# addr-bl.net
KiCad netlist of a schematic drawn in EAGLE
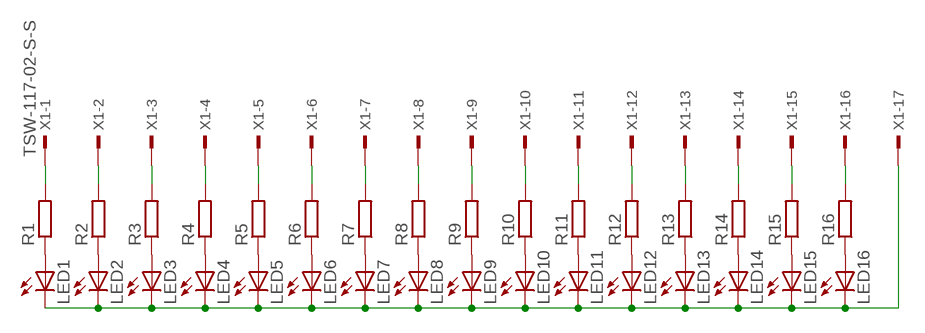
[diagram p0: schematic, sheet 1]

(export (version "E")
  (design (tool "Eeschema 10.0.6"))
  (components
    (comp (ref "LED1")
      (value "LEDSMT1206")
      (footprint "eagle-import:1206")
      (libsource (lib "eagle-import") (part "LEDSMT1206"))
    )
    (comp (ref "LED2")
      (value "LEDSMT1206")
      (footprint "eagle-import:1206")
      (libsource (lib "eagle-import") (part "LEDSMT1206"))
    )
    (comp (ref "LED3")
      (value "LEDSMT1206")
      (footprint "eagle-import:1206")
      (libsource (lib "eagle-import") (part "LEDSMT1206"))
    )
    (comp (ref "LED4")
      (value "LEDSMT1206")
      (footprint "eagle-import:1206")
      (libsource (lib "eagle-import") (part "LEDSMT1206"))
    )
    (comp (ref "LED5")
      (value "LEDSMT1206")
      (footprint "eagle-import:1206")
      (libsource (lib "eagle-import") (part "LEDSMT1206"))
    )
    (comp (ref "LED6")
      (value "LEDSMT1206")
      (footprint "eagle-import:1206")
      (libsource (lib "eagle-import") (part "LEDSMT1206"))
    )
    (comp (ref "LED7")
      (value "LEDSMT1206")
      (footprint "eagle-import:1206")
      (libsource (lib "eagle-import") (part "LEDSMT1206"))
    )
    (comp (ref "LED8")
      (value "LEDSMT1206")
      (footprint "eagle-import:1206")
      (libsource (lib "eagle-import") (part "LEDSMT1206"))
    )
    (comp (ref "LED9")
      (value "LEDSMT1206")
      (footprint "eagle-import:1206")
      (libsource (lib "eagle-import") (part "LEDSMT1206"))
    )
    (comp (ref "LED10")
      (value "LEDSMT1206")
      (footprint "eagle-import:1206")
      (libsource (lib "eagle-import") (part "LEDSMT1206"))
    )
    (comp (ref "LED11")
      (value "LEDSMT1206")
      (footprint "eagle-import:1206")
      (libsource (lib "eagle-import") (part "LEDSMT1206"))
    )
    (comp (ref "LED12")
      (value "LEDSMT1206")
      (footprint "eagle-import:1206")
      (libsource (lib "eagle-import") (part "LEDSMT1206"))
    )
    (comp (ref "LED13")
      (value "LEDSMT1206")
      (footprint "eagle-import:1206")
      (libsource (lib "eagle-import") (part "LEDSMT1206"))
    )
    (comp (ref "LED14")
      (value "LEDSMT1206")
      (footprint "eagle-import:1206")
      (libsource (lib "eagle-import") (part "LEDSMT1206"))
    )
    (comp (ref "LED15")
      (value "LEDSMT1206")
      (footprint "eagle-import:1206")
      (libsource (lib "eagle-import") (part "LEDSMT1206"))
    )
    (comp (ref "LED16")
      (value "LEDSMT1206")
      (footprint "eagle-import:1206")
      (libsource (lib "eagle-import") (part "LEDSMT1206"))
    )
    (comp (ref "R1")
      (value "R-EU_M1206")
      (footprint "eagle-import:M1206")
      (libsource (lib "eagle-import") (part "R-EU_M1206"))
    )
    (comp (ref "R2")
      (value "R-EU_M1206")
      (footprint "eagle-import:M1206")
      (libsource (lib "eagle-import") (part "R-EU_M1206"))
    )
    (comp (ref "R3")
      (value "R-EU_M1206")
      (footprint "eagle-import:M1206")
      (libsource (lib "eagle-import") (part "R-EU_M1206"))
    )
    (comp (ref "R4")
      (value "R-EU_M1206")
      (footprint "eagle-import:M1206")
      (libsource (lib "eagle-import") (part "R-EU_M1206"))
    )
    (comp (ref "R5")
      (value "R-EU_M1206")
      (footprint "eagle-import:M1206")
      (libsource (lib "eagle-import") (part "R-EU_M1206"))
    )
    (comp (ref "R6")
      (value "R-EU_M1206")
      (footprint "eagle-import:M1206")
      (libsource (lib "eagle-import") (part "R-EU_M1206"))
    )
    (comp (ref "R7")
      (value "R-EU_M1206")
      (footprint "eagle-import:M1206")
      (libsource (lib "eagle-import") (part "R-EU_M1206"))
    )
    (comp (ref "R8")
      (value "R-EU_M1206")
      (footprint "eagle-import:M1206")
      (libsource (lib "eagle-import") (part "R-EU_M1206"))
    )
    (comp (ref "R9")
      (value "R-EU_M1206")
      (footprint "eagle-import:M1206")
      (libsource (lib "eagle-import") (part "R-EU_M1206"))
    )
    (comp (ref "R10")
      (value "R-EU_M1206")
      (footprint "eagle-import:M1206")
      (libsource (lib "eagle-import") (part "R-EU_M1206"))
    )
    (comp (ref "R11")
      (value "R-EU_M1206")
      (footprint "eagle-import:M1206")
      (libsource (lib "eagle-import") (part "R-EU_M1206"))
    )
    (comp (ref "R12")
      (value "R-EU_M1206")
      (footprint "eagle-import:M1206")
      (libsource (lib "eagle-import") (part "R-EU_M1206"))
    )
    (comp (ref "R13")
      (value "R-EU_M1206")
      (footprint "eagle-import:M1206")
      (libsource (lib "eagle-import") (part "R-EU_M1206"))
    )
    (comp (ref "R14")
      (value "R-EU_M1206")
      (footprint "eagle-import:M1206")
      (libsource (lib "eagle-import") (part "R-EU_M1206"))
    )
    (comp (ref "R15")
      (value "R-EU_M1206")
      (footprint "eagle-import:M1206")
      (libsource (lib "eagle-import") (part "R-EU_M1206"))
    )
    (comp (ref "R16")
      (value "R-EU_M1206")
      (footprint "eagle-import:M1206")
      (libsource (lib "eagle-import") (part "R-EU_M1206"))
    )
    (comp (ref "X1")
      (value "TSW-117-02-S-S")
      (footprint "eagle-import:TSW-117-02-S-S")
      (libsource (lib "eagle-import") (part "TSW-117-02-S-S"))
    )
  )
  (nets
    (net (code "1") (name "Net-(LED1-PadA)") (class "Default")
      (node (ref "LED1") (pin "A") (pinfunction "A_A") (pintype "passive"))
      (node (ref "R1") (pin "1") (pinfunction "1_1") (pintype "passive"))
    )
    (net (code "2") (name "Net-(LED2-PadA)") (class "Default")
      (node (ref "LED2") (pin "A") (pinfunction "A_A") (pintype "passive"))
      (node (ref "R2") (pin "1") (pinfunction "1_1") (pintype "passive"))
    )
    (net (code "3") (name "Net-(LED3-PadA)") (class "Default")
      (node (ref "LED3") (pin "A") (pinfunction "A_A") (pintype "passive"))
      (node (ref "R3") (pin "1") (pinfunction "1_1") (pintype "passive"))
    )
    (net (code "4") (name "Net-(LED4-PadA)") (class "Default")
      (node (ref "LED4") (pin "A") (pinfunction "A_A") (pintype "passive"))
      (node (ref "R4") (pin "1") (pinfunction "1_1") (pintype "passive"))
    )
    (net (code "5") (name "Net-(LED5-PadA)") (class "Default")
      (node (ref "LED5") (pin "A") (pinfunction "A_A") (pintype "passive"))
      (node (ref "R5") (pin "1") (pinfunction "1_1") (pintype "passive"))
    )
    (net (code "6") (name "Net-(LED6-PadA)") (class "Default")
      (node (ref "LED6") (pin "A") (pinfunction "A_A") (pintype "passive"))
      (node (ref "R6") (pin "1") (pinfunction "1_1") (pintype "passive"))
    )
    (net (code "7") (name "Net-(LED7-PadA)") (class "Default")
      (node (ref "LED7") (pin "A") (pinfunction "A_A") (pintype "passive"))
      (node (ref "R7") (pin "1") (pinfunction "1_1") (pintype "passive"))
    )
    (net (code "8") (name "Net-(LED8-PadA)") (class "Default")
      (node (ref "LED8") (pin "A") (pinfunction "A_A") (pintype "passive"))
      (node (ref "R8") (pin "1") (pinfunction "1_1") (pintype "passive"))
    )
    (net (code "9") (name "Net-(LED9-PadA)") (class "Default")
      (node (ref "LED9") (pin "A") (pinfunction "A_A") (pintype "passive"))
      (node (ref "R9") (pin "1") (pinfunction "1_1") (pintype "passive"))
    )
    (net (code "10") (name "Net-(LED10-PadA)") (class "Default")
      (node (ref "LED10") (pin "A") (pinfunction "A_A") (pintype "passive"))
      (node (ref "R10") (pin "1") (pinfunction "1_1") (pintype "passive"))
    )
    (net (code "11") (name "Net-(LED11-PadA)") (class "Default")
      (node (ref "LED11") (pin "A") (pinfunction "A_A") (pintype "passive"))
      (node (ref "R11") (pin "1") (pinfunction "1_1") (pintype "passive"))
    )
    (net (code "12") (name "Net-(LED12-PadA)") (class "Default")
      (node (ref "LED12") (pin "A") (pinfunction "A_A") (pintype "passive"))
      (node (ref "R12") (pin "1") (pinfunction "1_1") (pintype "passive"))
    )
    (net (code "13") (name "Net-(LED13-PadA)") (class "Default")
      (node (ref "LED13") (pin "A") (pinfunction "A_A") (pintype "passive"))
      (node (ref "R13") (pin "1") (pinfunction "1_1") (pintype "passive"))
    )
    (net (code "14") (name "Net-(LED14-PadA)") (class "Default")
      (node (ref "LED14") (pin "A") (pinfunction "A_A") (pintype "passive"))
      (node (ref "R14") (pin "1") (pinfunction "1_1") (pintype "passive"))
    )
    (net (code "15") (name "Net-(LED15-PadA)") (class "Default")
      (node (ref "LED15") (pin "A") (pinfunction "A_A") (pintype "passive"))
      (node (ref "R15") (pin "1") (pinfunction "1_1") (pintype "passive"))
    )
    (net (code "16") (name "Net-(LED16-PadA)") (class "Default")
      (node (ref "LED16") (pin "A") (pinfunction "A_A") (pintype "passive"))
      (node (ref "R16") (pin "1") (pinfunction "1_1") (pintype "passive"))
    )
    (net (code "17") (name "Net-(R1-Pad2)") (class "Default")
      (node (ref "R1") (pin "2") (pinfunction "2_2") (pintype "passive"))
      (node (ref "X1") (pin "1") (pinfunction "1_1") (pintype "passive"))
    )
    (net (code "18") (name "Net-(X1B-1)") (class "Default")
      (node (ref "R10") (pin "2") (pinfunction "2_2") (pintype "passive"))
      (node (ref "X1") (pin "10") (pinfunction "1_10") (pintype "passive"))
    )
    (net (code "19") (name "Net-(X1C-1)") (class "Default")
      (node (ref "R11") (pin "2") (pinfunction "2_2") (pintype "passive"))
      (node (ref "X1") (pin "11") (pinfunction "1_11") (pintype "passive"))
    )
    (net (code "20") (name "Net-(X1D-1)") (class "Default")
      (node (ref "R12") (pin "2") (pinfunction "2_2") (pintype "passive"))
      (node (ref "X1") (pin "12") (pinfunction "1_12") (pintype "passive"))
    )
    (net (code "21") (name "Net-(X1E-1)") (class "Default")
      (node (ref "R13") (pin "2") (pinfunction "2_2") (pintype "passive"))
      (node (ref "X1") (pin "13") (pinfunction "1_13") (pintype "passive"))
    )
    (net (code "22") (name "Net-(X1F-1)") (class "Default")
      (node (ref "R14") (pin "2") (pinfunction "2_2") (pintype "passive"))
      (node (ref "X1") (pin "14") (pinfunction "1_14") (pintype "passive"))
    )
    (net (code "23") (name "Net-(X1G-1)") (class "Default")
      (node (ref "R15") (pin "2") (pinfunction "2_2") (pintype "passive"))
      (node (ref "X1") (pin "15") (pinfunction "1_15") (pintype "passive"))
    )
    (net (code "24") (name "Net-(X1H-1)") (class "Default")
      (node (ref "R16") (pin "2") (pinfunction "2_2") (pintype "passive"))
      (node (ref "X1") (pin "16") (pinfunction "1_16") (pintype "passive"))
    )
    (net (code "25") (name "Net-(X1I-1)") (class "Default")
      (node (ref "LED1") (pin "C") (pinfunction "C_C") (pintype "passive"))
      (node (ref "LED10") (pin "C") (pinfunction "C_C") (pintype "passive"))
      (node (ref "LED11") (pin "C") (pinfunction "C_C") (pintype "passive"))
      (node (ref "LED12") (pin "C") (pinfunction "C_C") (pintype "passive"))
      (node (ref "LED13") (pin "C") (pinfunction "C_C") (pintype "passive"))
      (node (ref "LED14") (pin "C") (pinfunction "C_C") (pintype "passive"))
      (node (ref "LED15") (pin "C") (pinfunction "C_C") (pintype "passive"))
      (node (ref "LED16") (pin "C") (pinfunction "C_C") (pintype "passive"))
      (node (ref "LED2") (pin "C") (pinfunction "C_C") (pintype "passive"))
      (node (ref "LED3") (pin "C") (pinfunction "C_C") (pintype "passive"))
      (node (ref "LED4") (pin "C") (pinfunction "C_C") (pintype "passive"))
      (node (ref "LED5") (pin "C") (pinfunction "C_C") (pintype "passive"))
      (node (ref "LED6") (pin "C") (pinfunction "C_C") (pintype "passive"))
      (node (ref "LED7") (pin "C") (pinfunction "C_C") (pintype "passive"))
      (node (ref "LED8") (pin "C") (pinfunction "C_C") (pintype "passive"))
      (node (ref "LED9") (pin "C") (pinfunction "C_C") (pintype "passive"))
      (node (ref "X1") (pin "17") (pinfunction "1_17") (pintype "passive"))
    )
    (net (code "26") (name "Net-(X1J-1)") (class "Default")
      (node (ref "R2") (pin "2") (pinfunction "2_2") (pintype "passive"))
      (node (ref "X1") (pin "2") (pinfunction "1_2") (pintype "passive"))
    )
    (net (code "27") (name "Net-(X1K-1)") (class "Default")
      (node (ref "R3") (pin "2") (pinfunction "2_2") (pintype "passive"))
      (node (ref "X1") (pin "3") (pinfunction "1_3") (pintype "passive"))
    )
    (net (code "28") (name "Net-(X1L-1)") (class "Default")
      (node (ref "R4") (pin "2") (pinfunction "2_2") (pintype "passive"))
      (node (ref "X1") (pin "4") (pinfunction "1_4") (pintype "passive"))
    )
    (net (code "29") (name "Net-(X1M-1)") (class "Default")
      (node (ref "R5") (pin "2") (pinfunction "2_2") (pintype "passive"))
      (node (ref "X1") (pin "5") (pinfunction "1_5") (pintype "passive"))
    )
    (net (code "30") (name "Net-(X1N-1)") (class "Default")
      (node (ref "R6") (pin "2") (pinfunction "2_2") (pintype "passive"))
      (node (ref "X1") (pin "6") (pinfunction "1_6") (pintype "passive"))
    )
    (net (code "31") (name "Net-(X1O-1)") (class "Default")
      (node (ref "R7") (pin "2") (pinfunction "2_2") (pintype "passive"))
      (node (ref "X1") (pin "7") (pinfunction "1_7") (pintype "passive"))
    )
    (net (code "32") (name "Net-(X1P-1)") (class "Default")
      (node (ref "R8") (pin "2") (pinfunction "2_2") (pintype "passive"))
      (node (ref "X1") (pin "8") (pinfunction "1_8") (pintype "passive"))
    )
    (net (code "33") (name "Net-(X1Q-1)") (class "Default")
      (node (ref "R9") (pin "2") (pinfunction "2_2") (pintype "passive"))
      (node (ref "X1") (pin "9") (pinfunction "1_9") (pintype "passive"))
    )
  )
)
